# WS2811Verst_rker.net
KiCad netlist of a schematic drawn in EAGLE
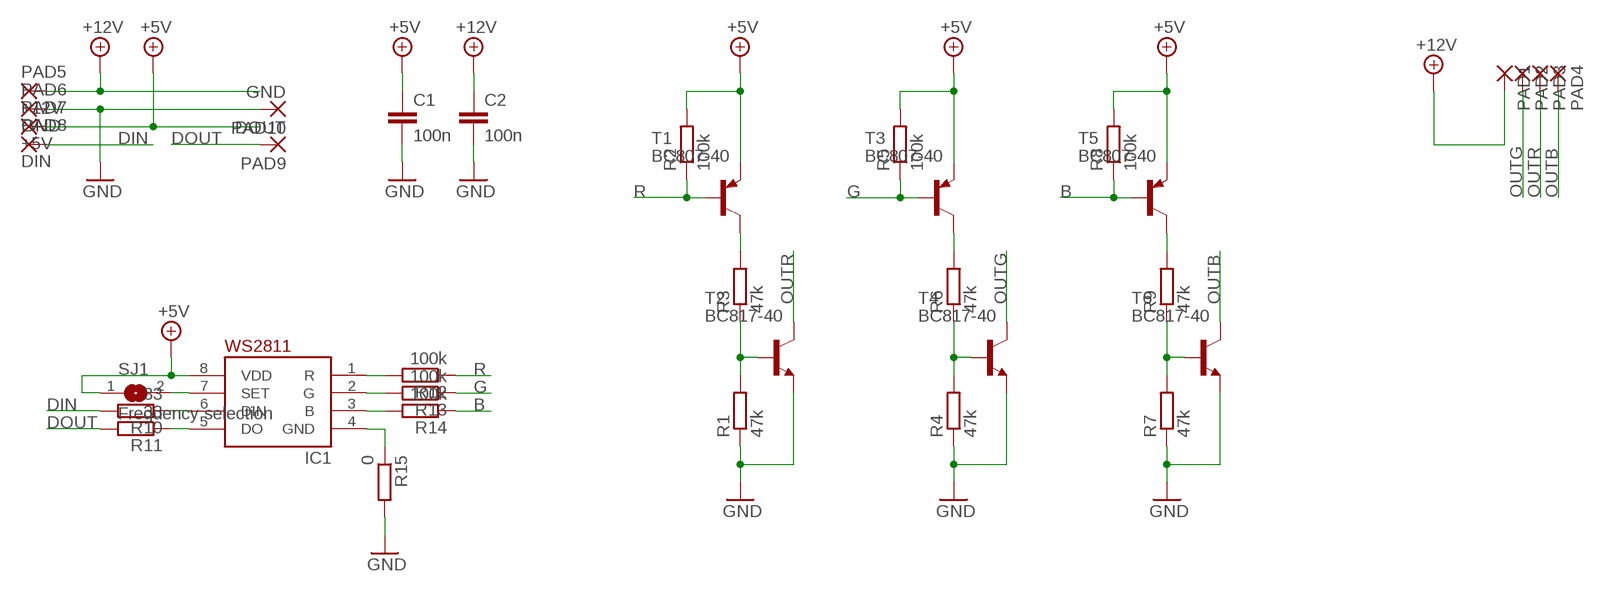
[diagram p0: schematic, sheet 1]

(export (version "E")
  (design (tool "Eeschema 10.0.6"))
  (components
    (comp (ref "C1")
      (value "100n")
      (footprint "eagle-import:C1206")
      (libsource (lib "eagle-import") (part "C-EUC1206"))
    )
    (comp (ref "C2")
      (value "100n")
      (footprint "eagle-import:C1206")
      (libsource (lib "eagle-import") (part "C-EUC1206"))
    )
    (comp (ref "IC1")
      (value "WS2811-SOP8")
      (footprint "eagle-import:SO08-SKINNYPADS")
      (libsource (lib "eagle-import") (part "WS2811-SOP8"))
    )
    (comp (ref "PAD1")
      (value "SMD5")
      (footprint "eagle-import:SMD2,54-5,08")
      (libsource (lib "eagle-import") (part "SMD5"))
    )
    (comp (ref "PAD2")
      (value "SMD5")
      (footprint "eagle-import:SMD2,54-5,08")
      (libsource (lib "eagle-import") (part "SMD5"))
    )
    (comp (ref "PAD3")
      (value "SMD5")
      (footprint "eagle-import:SMD2,54-5,08")
      (libsource (lib "eagle-import") (part "SMD5"))
    )
    (comp (ref "PAD4")
      (value "SMD5")
      (footprint "eagle-import:SMD2,54-5,08")
      (libsource (lib "eagle-import") (part "SMD5"))
    )
    (comp (ref "PAD5")
      (value "+12V")
      (footprint "eagle-import:SMD2,54-5,08")
      (libsource (lib "eagle-import") (part "SMD5"))
    )
    (comp (ref "PAD6")
      (value "GND")
      (footprint "eagle-import:SMD2,54-5,08")
      (libsource (lib "eagle-import") (part "SMD5"))
    )
    (comp (ref "PAD7")
      (value "+5V")
      (footprint "eagle-import:SMD2,54-5,08")
      (libsource (lib "eagle-import") (part "SMD5"))
    )
    (comp (ref "PAD8")
      (value "DIN")
      (footprint "eagle-import:SMD2,54-5,08")
      (libsource (lib "eagle-import") (part "SMD5"))
    )
    (comp (ref "PAD9")
      (value "DOUT")
      (footprint "eagle-import:SMD2,54-5,08")
      (libsource (lib "eagle-import") (part "SMD5"))
    )
    (comp (ref "PAD10")
      (value "GND")
      (footprint "eagle-import:SMD2,54-5,08")
      (libsource (lib "eagle-import") (part "SMD5"))
    )
    (comp (ref "R1")
      (value "47k")
      (footprint "eagle-import:R1206")
      (libsource (lib "eagle-import") (part "R-EU_R1206"))
    )
    (comp (ref "R2")
      (value "100k")
      (footprint "eagle-import:R1206")
      (libsource (lib "eagle-import") (part "R-EU_R1206"))
    )
    (comp (ref "R3")
      (value "47k")
      (footprint "eagle-import:R1206")
      (libsource (lib "eagle-import") (part "R-EU_R1206"))
    )
    (comp (ref "R4")
      (value "47k")
      (footprint "eagle-import:R1206")
      (libsource (lib "eagle-import") (part "R-EU_R1206"))
    )
    (comp (ref "R5")
      (value "100k")
      (footprint "eagle-import:R1206")
      (libsource (lib "eagle-import") (part "R-EU_R1206"))
    )
    (comp (ref "R6")
      (value "47k")
      (footprint "eagle-import:R1206")
      (libsource (lib "eagle-import") (part "R-EU_R1206"))
    )
    (comp (ref "R7")
      (value "47k")
      (footprint "eagle-import:R1206")
      (libsource (lib "eagle-import") (part "R-EU_R1206"))
    )
    (comp (ref "R8")
      (value "100k")
      (footprint "eagle-import:R1206")
      (libsource (lib "eagle-import") (part "R-EU_R1206"))
    )
    (comp (ref "R9")
      (value "47k")
      (footprint "eagle-import:R1206")
      (libsource (lib "eagle-import") (part "R-EU_R1206"))
    )
    (comp (ref "R10")
      (value "33")
      (footprint "eagle-import:R1206")
      (libsource (lib "eagle-import") (part "R-EU_R1206"))
    )
    (comp (ref "R11")
      (value "33")
      (footprint "eagle-import:R1206")
      (libsource (lib "eagle-import") (part "R-EU_R1206"))
    )
    (comp (ref "R12")
      (value "100k")
      (footprint "eagle-import:R1206")
      (libsource (lib "eagle-import") (part "R-EU_R1206"))
    )
    (comp (ref "R13")
      (value "100k")
      (footprint "eagle-import:R1206")
      (libsource (lib "eagle-import") (part "R-EU_R1206"))
    )
    (comp (ref "R14")
      (value "100k")
      (footprint "eagle-import:R1206")
      (libsource (lib "eagle-import") (part "R-EU_R1206"))
    )
    (comp (ref "R15")
      (value "0")
      (footprint "eagle-import:R1206")
      (libsource (lib "eagle-import") (part "R-EU_R1206"))
    )
    (comp (ref "SJ1")
      (value "Frequency selection")
      (footprint "eagle-import:SJ")
      (libsource (lib "eagle-import") (part "SJ"))
    )
    (comp (ref "T1")
      (value "BC807-40")
      (footprint "eagle-import:SOT23-BEC")
      (libsource (lib "eagle-import") (part "-PNP-SOT23-BECBC807-40"))
    )
    (comp (ref "T2")
      (value "BC817-40")
      (footprint "eagle-import:SOT23-BEC")
      (libsource (lib "eagle-import") (part "-NPN-SOT23-BECBC817-40"))
    )
    (comp (ref "T3")
      (value "BC807-40")
      (footprint "eagle-import:SOT23-BEC")
      (libsource (lib "eagle-import") (part "-PNP-SOT23-BECBC807-40"))
    )
    (comp (ref "T4")
      (value "BC817-40")
      (footprint "eagle-import:SOT23-BEC")
      (libsource (lib "eagle-import") (part "-NPN-SOT23-BECBC817-40"))
    )
    (comp (ref "T5")
      (value "BC807-40")
      (footprint "eagle-import:SOT23-BEC")
      (libsource (lib "eagle-import") (part "-PNP-SOT23-BECBC807-40"))
    )
    (comp (ref "T6")
      (value "BC817-40")
      (footprint "eagle-import:SOT23-BEC")
      (libsource (lib "eagle-import") (part "-NPN-SOT23-BECBC817-40"))
    )
  )
  (nets
    (net (code "1") (name "+5V") (class "Default")
      (node (ref "C1") (pin "1") (pinfunction "1_1") (pintype "passive"))
      (node (ref "IC1") (pin "8") (pinfunction "VDD_8") (pintype "power_in"))
      (node (ref "PAD7") (pin "1") (pinfunction "P_1") (pintype "passive"))
      (node (ref "R2") (pin "2") (pinfunction "2_2") (pintype "passive"))
      (node (ref "R5") (pin "2") (pinfunction "2_2") (pintype "passive"))
      (node (ref "R8") (pin "2") (pinfunction "2_2") (pintype "passive"))
      (node (ref "SJ1") (pin "1") (pinfunction "1_1") (pintype "passive"))
      (node (ref "T1") (pin "E") (pinfunction "E_E") (pintype "passive"))
      (node (ref "T3") (pin "E") (pinfunction "E_E") (pintype "passive"))
      (node (ref "T5") (pin "E") (pinfunction "E_E") (pintype "passive"))
    )
    (net (code "2") (name "+12V") (class "Default")
      (node (ref "C2") (pin "1") (pinfunction "1_1") (pintype "passive"))
      (node (ref "PAD1") (pin "1") (pinfunction "P_1") (pintype "passive"))
      (node (ref "PAD5") (pin "1") (pinfunction "P_1") (pintype "passive"))
    )
    (net (code "3") (name "/B") (class "Default")
      (node (ref "R14") (pin "1") (pinfunction "1_1") (pintype "passive"))
      (node (ref "R8") (pin "1") (pinfunction "1_1") (pintype "passive"))
      (node (ref "T5") (pin "B") (pinfunction "B_B") (pintype "passive"))
    )
    (net (code "4") (name "/DIN") (class "Default")
      (node (ref "PAD8") (pin "1") (pinfunction "P_1") (pintype "passive"))
      (node (ref "R10") (pin "2") (pinfunction "2_2") (pintype "passive"))
    )
    (net (code "5") (name "/DOUT") (class "Default")
      (node (ref "PAD9") (pin "1") (pinfunction "P_1") (pintype "passive"))
      (node (ref "R11") (pin "2") (pinfunction "2_2") (pintype "passive"))
    )
    (net (code "6") (name "/G") (class "Default")
      (node (ref "R13") (pin "1") (pinfunction "1_1") (pintype "passive"))
      (node (ref "R5") (pin "1") (pinfunction "1_1") (pintype "passive"))
      (node (ref "T3") (pin "B") (pinfunction "B_B") (pintype "passive"))
    )
    (net (code "7") (name "/OUTB") (class "Default")
      (node (ref "PAD4") (pin "1") (pinfunction "P_1") (pintype "passive"))
      (node (ref "T6") (pin "C") (pinfunction "C_C") (pintype "passive"))
    )
    (net (code "8") (name "/OUTG") (class "Default")
      (node (ref "PAD2") (pin "1") (pinfunction "P_1") (pintype "passive"))
      (node (ref "T4") (pin "C") (pinfunction "C_C") (pintype "passive"))
    )
    (net (code "9") (name "/OUTR") (class "Default")
      (node (ref "PAD3") (pin "1") (pinfunction "P_1") (pintype "passive"))
      (node (ref "T2") (pin "C") (pinfunction "C_C") (pintype "passive"))
    )
    (net (code "10") (name "/R") (class "Default")
      (node (ref "R12") (pin "1") (pinfunction "1_1") (pintype "passive"))
      (node (ref "R2") (pin "1") (pinfunction "1_1") (pintype "passive"))
      (node (ref "T1") (pin "B") (pinfunction "B_B") (pintype "passive"))
    )
    (net (code "11") (name "GND") (class "Default")
      (node (ref "C1") (pin "2") (pinfunction "2_2") (pintype "passive"))
      (node (ref "C2") (pin "2") (pinfunction "2_2") (pintype "passive"))
      (node (ref "PAD10") (pin "1") (pinfunction "P_1") (pintype "passive"))
      (node (ref "PAD6") (pin "1") (pinfunction "P_1") (pintype "passive"))
      (node (ref "R1") (pin "1") (pinfunction "1_1") (pintype "passive"))
      (node (ref "R15") (pin "2") (pinfunction "2_2") (pintype "passive"))
      (node (ref "R4") (pin "1") (pinfunction "1_1") (pintype "passive"))
      (node (ref "R7") (pin "1") (pinfunction "1_1") (pintype "passive"))
      (node (ref "T2") (pin "E") (pinfunction "E_E") (pintype "passive"))
      (node (ref "T4") (pin "E") (pinfunction "E_E") (pintype "passive"))
      (node (ref "T6") (pin "E") (pinfunction "E_E") (pintype "passive"))
    )
    (net (code "12") (name "Net-(IC1-B)") (class "Default")
      (node (ref "IC1") (pin "3") (pinfunction "B_3") (pintype "open_collector"))
      (node (ref "R14") (pin "2") (pinfunction "2_2") (pintype "passive"))
    )
    (net (code "13") (name "Net-(IC1-DIN)") (class "Default")
      (node (ref "IC1") (pin "6") (pinfunction "DIN_6") (pintype "input"))
      (node (ref "R10") (pin "1") (pinfunction "1_1") (pintype "passive"))
    )
    (net (code "14") (name "Net-(IC1-DO)") (class "Default")
      (node (ref "IC1") (pin "5") (pinfunction "DO_5") (pintype "output"))
      (node (ref "R11") (pin "1") (pinfunction "1_1") (pintype "passive"))
    )
    (net (code "15") (name "Net-(IC1-G)") (class "Default")
      (node (ref "IC1") (pin "2") (pinfunction "G_2") (pintype "open_collector"))
      (node (ref "R13") (pin "2") (pinfunction "2_2") (pintype "passive"))
    )
    (net (code "16") (name "Net-(IC1-GND)") (class "Default")
      (node (ref "IC1") (pin "4") (pinfunction "GND_4") (pintype "power_in"))
      (node (ref "R15") (pin "1") (pinfunction "1_1") (pintype "passive"))
    )
    (net (code "17") (name "Net-(IC1-R)") (class "Default")
      (node (ref "IC1") (pin "1") (pinfunction "R_1") (pintype "open_collector"))
      (node (ref "R12") (pin "2") (pinfunction "2_2") (pintype "passive"))
    )
    (net (code "18") (name "Net-(IC1-SET)") (class "Default")
      (node (ref "IC1") (pin "7") (pinfunction "SET_7") (pintype "input"))
      (node (ref "SJ1") (pin "2") (pinfunction "2_2") (pintype "passive"))
    )
    (net (code "19") (name "Net-(R1-Pad2)") (class "Default")
      (node (ref "R1") (pin "2") (pinfunction "2_2") (pintype "passive"))
      (node (ref "R3") (pin "1") (pinfunction "1_1") (pintype "passive"))
      (node (ref "T2") (pin "B") (pinfunction "B_B") (pintype "passive"))
    )
    (net (code "20") (name "Net-(R3-Pad2)") (class "Default")
      (node (ref "R3") (pin "2") (pinfunction "2_2") (pintype "passive"))
      (node (ref "T1") (pin "C") (pinfunction "C_C") (pintype "passive"))
    )
    (net (code "21") (name "Net-(R4-Pad2)") (class "Default")
      (node (ref "R4") (pin "2") (pinfunction "2_2") (pintype "passive"))
      (node (ref "R6") (pin "1") (pinfunction "1_1") (pintype "passive"))
      (node (ref "T4") (pin "B") (pinfunction "B_B") (pintype "passive"))
    )
    (net (code "22") (name "Net-(R6-Pad2)") (class "Default")
      (node (ref "R6") (pin "2") (pinfunction "2_2") (pintype "passive"))
      (node (ref "T3") (pin "C") (pinfunction "C_C") (pintype "passive"))
    )
    (net (code "23") (name "Net-(R7-Pad2)") (class "Default")
      (node (ref "R7") (pin "2") (pinfunction "2_2") (pintype "passive"))
      (node (ref "R9") (pin "1") (pinfunction "1_1") (pintype "passive"))
      (node (ref "T6") (pin "B") (pinfunction "B_B") (pintype "passive"))
    )
    (net (code "24") (name "Net-(R9-Pad2)") (class "Default")
      (node (ref "R9") (pin "2") (pinfunction "2_2") (pintype "passive"))
      (node (ref "T5") (pin "C") (pinfunction "C_C") (pintype "passive"))
    )
  )
)
